# CEM-8bit-PCF8574.net
KiCad netlist of a schematic drawn in EAGLE
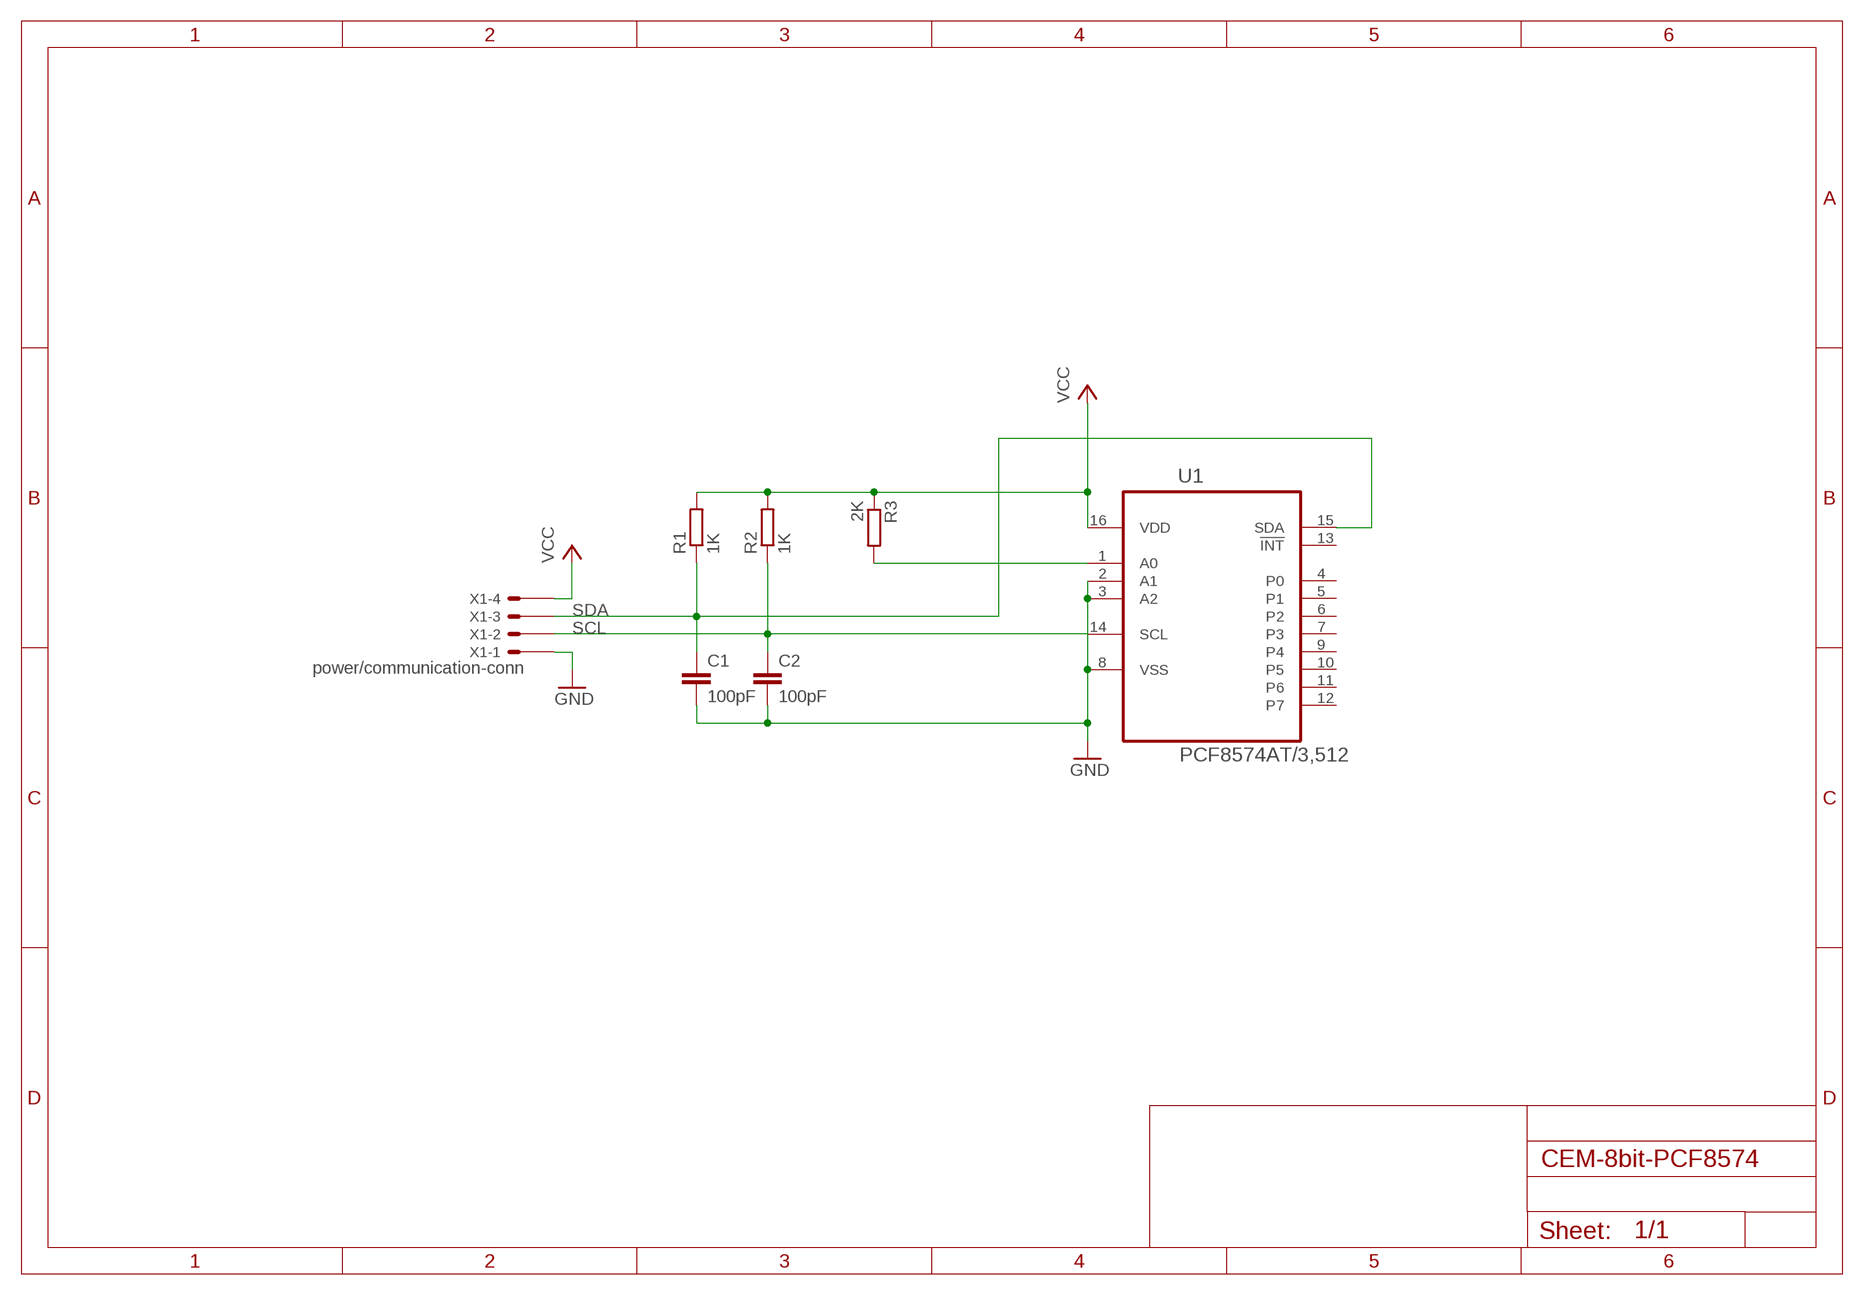
[diagram p0: schematic, sheet 1]

(export (version "E")
  (design (tool "Eeschema 10.0.6"))
  (components
    (comp (ref "C1")
      (value "100pF")
      (footprint "eagle-import:C0805K")
      (libsource (lib "eagle-import") (part "C-EUC0805K"))
    )
    (comp (ref "C2")
      (value "100pF")
      (footprint "eagle-import:C0805K")
      (libsource (lib "eagle-import") (part "C-EUC0805K"))
    )
    (comp (ref "R1")
      (value "1K")
      (footprint "eagle-import:M1406")
      (libsource (lib "eagle-import") (part "R-EU_M1406"))
    )
    (comp (ref "R2")
      (value "1K")
      (footprint "eagle-import:M1406")
      (libsource (lib "eagle-import") (part "R-EU_M1406"))
    )
    (comp (ref "R3")
      (value "2K")
      (footprint "eagle-import:M1406")
      (libsource (lib "eagle-import") (part "R-EU_M1406"))
    )
    (comp (ref "U1")
      (value "PCF8574AT/3,512")
      (footprint "eagle-import:SOIC127P1032X265-16N")
      (libsource (lib "eagle-import") (part "PCF8574AT/3,512"))
    )
    (comp (ref "X1")
      (value "power/communication-conn")
      (footprint "eagle-import:43160-XX04")
      (libsource (lib "eagle-import") (part "43160-0412"))
    )
  )
  (nets
    (net (code "1") (name "/SCL") (class "Default")
      (node (ref "C2") (pin "1") (pinfunction "1_1") (pintype "passive"))
      (node (ref "R2") (pin "1") (pinfunction "1_1") (pintype "passive"))
      (node (ref "U1") (pin "14") (pinfunction "SCL_14") (pintype "input"))
      (node (ref "X1") (pin "2@1") (pinfunction "S_2@1") (pintype "passive"))
    )
    (net (code "2") (name "/SDA") (class "Default")
      (node (ref "C1") (pin "1") (pinfunction "1_1") (pintype "passive"))
      (node (ref "R1") (pin "1") (pinfunction "1_1") (pintype "passive"))
      (node (ref "U1") (pin "15") (pinfunction "SDA_15") (pintype "bidirectional"))
      (node (ref "X1") (pin "3@1") (pinfunction "S_3@1") (pintype "passive"))
    )
    (net (code "3") (name "GND") (class "Default")
      (node (ref "C1") (pin "2") (pinfunction "2_2") (pintype "passive"))
      (node (ref "C2") (pin "2") (pinfunction "2_2") (pintype "passive"))
      (node (ref "U1") (pin "2") (pinfunction "A1_2") (pintype "input"))
      (node (ref "U1") (pin "3") (pinfunction "A2_3") (pintype "input"))
      (node (ref "U1") (pin "8") (pinfunction "VSS_8") (pintype "passive"))
      (node (ref "X1") (pin "1@1") (pinfunction "S_1@1") (pintype "passive"))
    )
    (net (code "4") (name "Net-(U1-A0)") (class "Default")
      (node (ref "R3") (pin "2") (pinfunction "2_2") (pintype "passive"))
      (node (ref "U1") (pin "1") (pinfunction "A0_1") (pintype "input"))
    )
    (net (code "5") (name "VCC") (class "Default")
      (node (ref "R1") (pin "2") (pinfunction "2_2") (pintype "passive"))
      (node (ref "R2") (pin "2") (pinfunction "2_2") (pintype "passive"))
      (node (ref "R3") (pin "1") (pinfunction "1_1") (pintype "passive"))
      (node (ref "U1") (pin "16") (pinfunction "VDD_16") (pintype "power_in"))
      (node (ref "X1") (pin "4@1") (pinfunction "S_4@1") (pintype "passive"))
    )
    (net (code "6") (name "unconnected-(U1-P0-Pad4)") (class "Default")
      (node (ref "U1") (pin "4") (pinfunction "P0_4") (pintype "bidirectional"))
    )
    (net (code "7") (name "unconnected-(U1-P1-Pad5)") (class "Default")
      (node (ref "U1") (pin "5") (pinfunction "P1_5") (pintype "bidirectional"))
    )
    (net (code "8") (name "unconnected-(U1-P2-Pad6)") (class "Default")
      (node (ref "U1") (pin "6") (pinfunction "P2_6") (pintype "bidirectional"))
    )
    (net (code "9") (name "unconnected-(U1-P3-Pad7)") (class "Default")
      (node (ref "U1") (pin "7") (pinfunction "P3_7") (pintype "bidirectional"))
    )
    (net (code "10") (name "unconnected-(U1-P4-Pad9)") (class "Default")
      (node (ref "U1") (pin "9") (pinfunction "P4_9") (pintype "bidirectional"))
    )
    (net (code "11") (name "unconnected-(U1-P5-Pad10)") (class "Default")
      (node (ref "U1") (pin "10") (pinfunction "P5_10") (pintype "bidirectional"))
    )
    (net (code "12") (name "unconnected-(U1-P6-Pad11)") (class "Default")
      (node (ref "U1") (pin "11") (pinfunction "P6_11") (pintype "bidirectional"))
    )
    (net (code "13") (name "unconnected-(U1-P7-Pad12)") (class "Default")
      (node (ref "U1") (pin "12") (pinfunction "P7_12") (pintype "bidirectional"))
    )
    (net (code "14") (name "unconnected-(U1-~{INT}-Pad13)") (class "Default")
      (node (ref "U1") (pin "13") (pinfunction "~{INT}_13") (pintype "output"))
    )
    (net (code "15") (name "unconnected-(X1A-S-Pad1@2)") (class "Default")
      (node (ref "X1") (pin "1@2") (pinfunction "S_1@2") (pintype "passive"))
    )
    (net (code "16") (name "unconnected-(X1B-S-Pad2@2)") (class "Default")
      (node (ref "X1") (pin "2@2") (pinfunction "S_2@2") (pintype "passive"))
    )
    (net (code "17") (name "unconnected-(X1C-S-Pad3@2)") (class "Default")
      (node (ref "X1") (pin "3@2") (pinfunction "S_3@2") (pintype "passive"))
    )
    (net (code "18") (name "unconnected-(X1D-S-Pad4@2)") (class "Default")
      (node (ref "X1") (pin "4@2") (pinfunction "S_4@2") (pintype "passive"))
    )
  )
)
